# roundboard_-_MDBT42Q_ICM20848_new.net
KiCad netlist of a schematic drawn in EAGLE
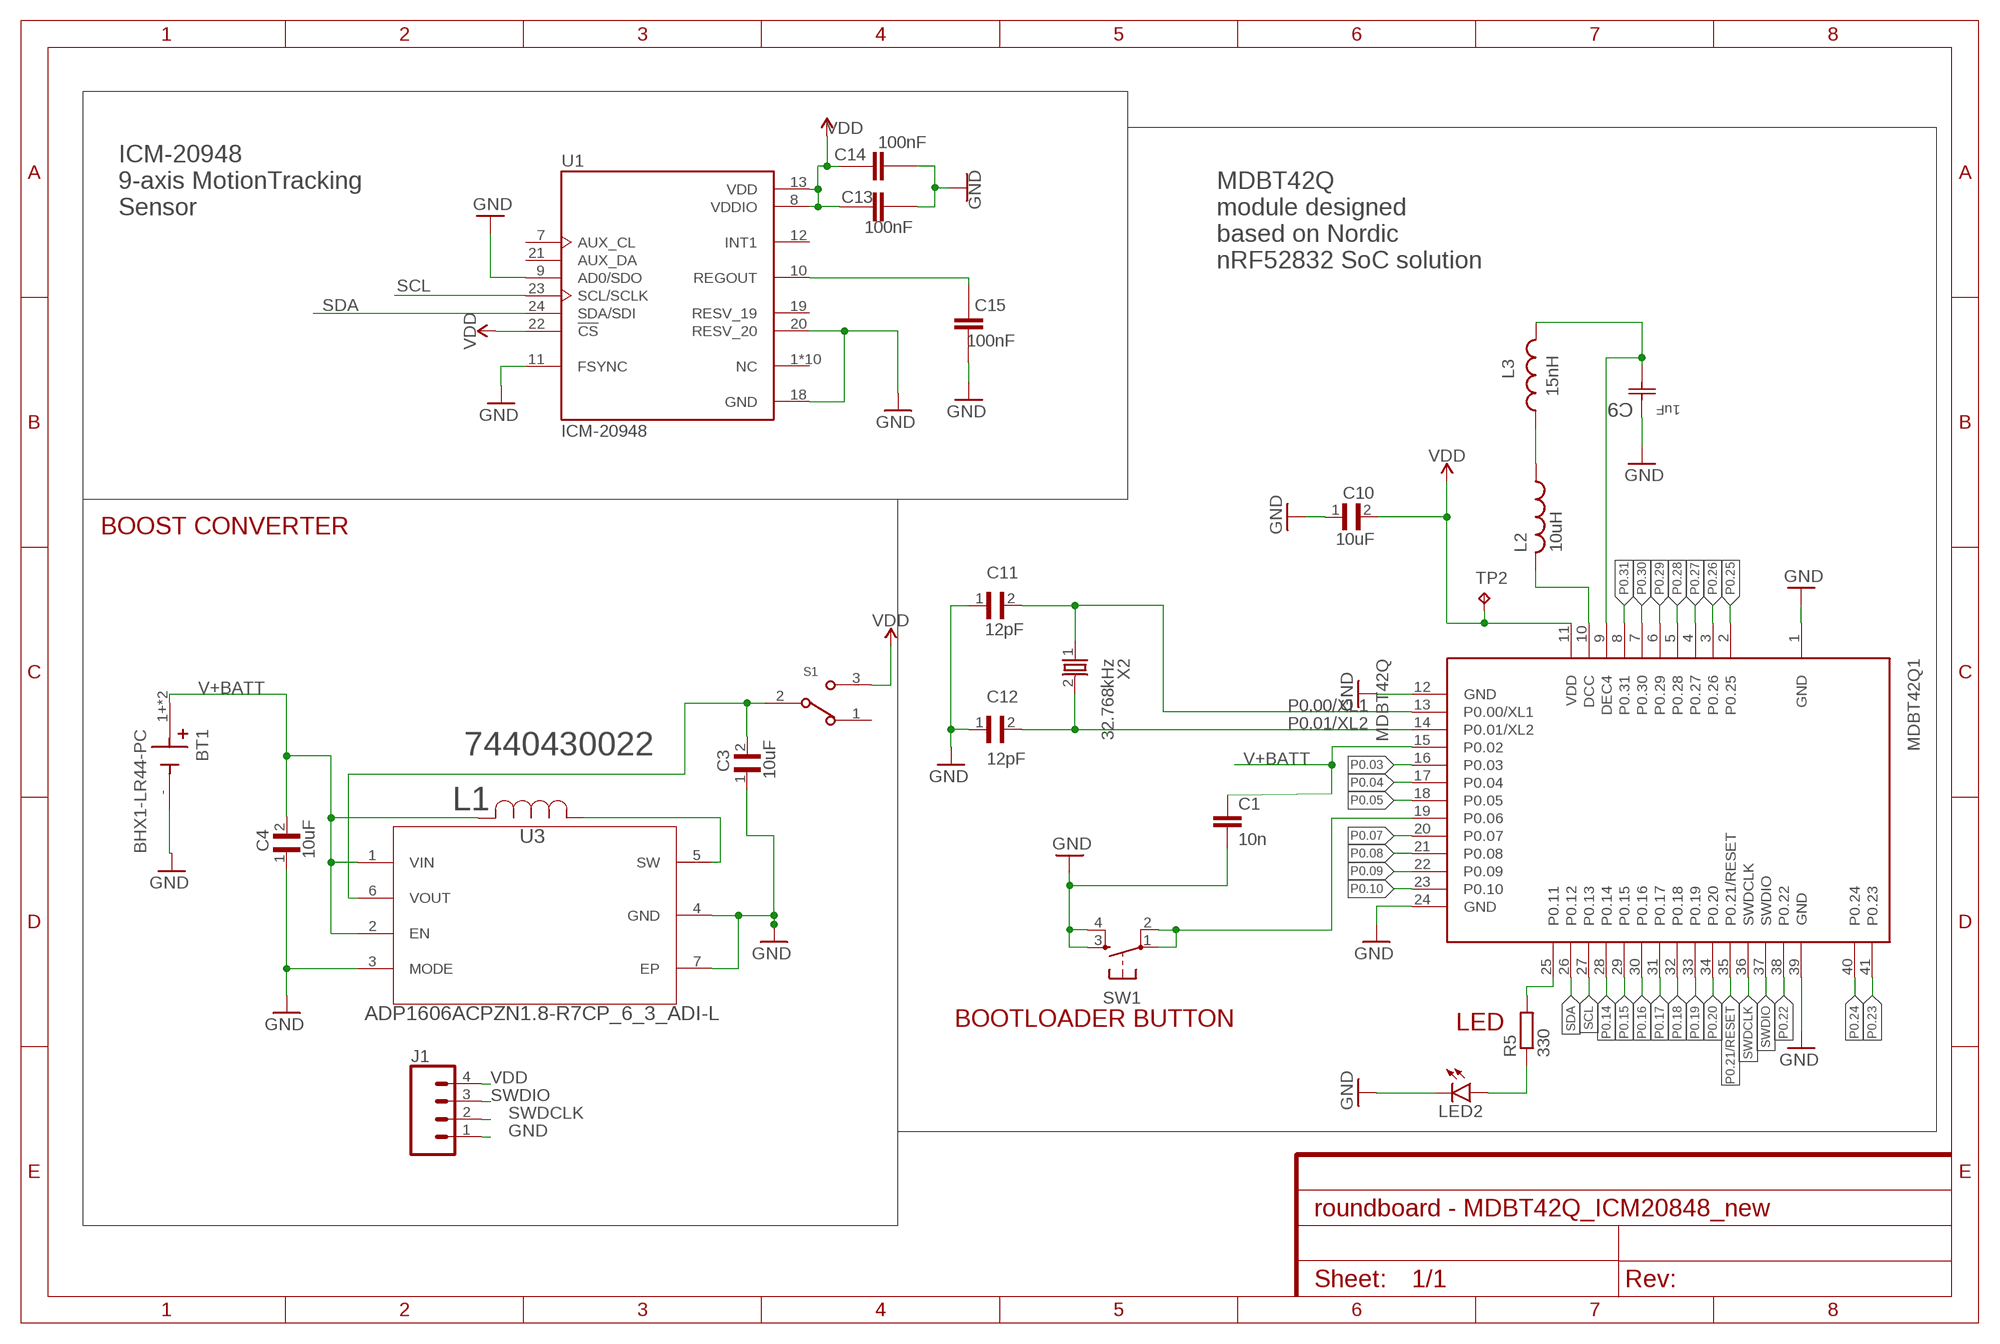
[diagram p0: schematic, sheet 1]

(export (version "E")
  (design (tool "Eeschema 10.0.6"))
  (components
    (comp (ref "BT1")
      (value "BHX1-LR44-PC")
      (footprint "eagle-import:BAT_BHX1-LR44-PC")
      (fields (field (name "DIGI-KEY_PART_NUMBER") "BHX1-LR44-PC-G-ND") (field (name "MF") "MPD"))
      (libsource (lib "eagle-import") (part "BHX1-LR44-PC"))
    )
    (comp (ref "C1")
      (value "10n")
      (footprint "eagle-import:C0603")
      (libsource (lib "eagle-import") (part "C-EUC0603"))
    )
    (comp (ref "C3")
      (value "10uF")
      (footprint "eagle-import:CAPC1608X95N")
      (fields
        (field (name "DIGI-KEY_PART_NUMBER") "490-14372-1-ND")
        (field (name "MF") "Murata")
        (field (name "MP") "GRM188R61A106KE69J")
      )
      (libsource (lib "eagle-import") (part "GRM188R61A106KE69J"))
    )
    (comp (ref "C4")
      (value "10uF")
      (footprint "eagle-import:CAPC1608X95N")
      (fields
        (field (name "DIGI-KEY_PART_NUMBER") "490-14372-1-ND")
        (field (name "MF") "Murata")
        (field (name "MP") "GRM188R61A106KE69J")
      )
      (libsource (lib "eagle-import") (part "GRM188R61A106KE69J"))
    )
    (comp (ref "C9")
      (value "1uF")
      (footprint "eagle-import:CAPC1608X90N")
      (fields
        (field (name "DIGI-KEY_PART_NUMBER") "311-1446-1-ND")
        (field (name "MF") "Yageo")
        (field (name "MP") "CC0603KRX7R7BB105")
      )
      (libsource (lib "eagle-import") (part "CC0603KRX7R7BB105"))
    )
    (comp (ref "C10")
      (value "10uF")
      (footprint "eagle-import:CAPC1608X95N")
      (fields
        (field (name "DIGI-KEY_PART_NUMBER") "490-14372-1-ND")
        (field (name "MF") "Murata")
        (field (name "MP") "GRM188R61A106KE69J")
      )
      (libsource (lib "eagle-import") (part "GRM188R61A106KE69J"))
    )
    (comp (ref "C11")
      (value "12pF")
      (footprint "eagle-import:CAPC1005X56N")
      (fields
        (field (name "DIGI-KEY_PART_NUMBER") "478-7871-1-ND")
        (field (name "MF") "AVX")
        (field (name "MP") "04025A120GAT2A")
      )
      (libsource (lib "eagle-import") (part "04025A120GAT2A"))
    )
    (comp (ref "C12")
      (value "12pF")
      (footprint "eagle-import:CAPC1005X56N")
      (fields
        (field (name "DIGI-KEY_PART_NUMBER") "478-7871-1-ND")
        (field (name "MF") "AVX")
        (field (name "MP") "04025A120GAT2A")
      )
      (libsource (lib "eagle-import") (part "04025A120GAT2A"))
    )
    (comp (ref "C13")
      (value "100nF")
      (footprint "eagle-import:CAPC1005X60")
      (fields
        (field (name "DIGI-KEY_PART_NUMBER") "311-1345-1-ND")
        (field (name "MF") "Yageo")
        (field (name "MP") "CC0402KRX7R6BB104")
      )
      (libsource (lib "eagle-import") (part "CC0402KRX7R6BB104"))
    )
    (comp (ref "C14")
      (value "100nF")
      (footprint "eagle-import:CAPC1005X60")
      (fields
        (field (name "DIGI-KEY_PART_NUMBER") "311-1345-1-ND")
        (field (name "MF") "Yageo")
        (field (name "MP") "CC0402KRX7R6BB104")
      )
      (libsource (lib "eagle-import") (part "CC0402KRX7R6BB104"))
    )
    (comp (ref "C15")
      (value "100nF")
      (footprint "eagle-import:CAPC1005X60")
      (fields
        (field (name "DIGI-KEY_PART_NUMBER") "311-1345-1-ND")
        (field (name "MF") "Yageo")
        (field (name "MP") "CC0402KRX7R6BB104")
      )
      (libsource (lib "eagle-import") (part "CC0402KRX7R6BB104"))
    )
    (comp (ref "J1")
      (value "CONN_04PTH")
      (footprint "eagle-import:1X04")
      (libsource (lib "eagle-import") (part "CONN_04PTH"))
    )
    (comp (ref "L1")
      (value "7440430022")
      (footprint "eagle-import:IND_7440430022_WRE")
      (fields (field (name "COPYRIGHT") "Copyright (C) 2018 Accelerated Designs. All rights reserved"))
      (libsource (lib "eagle-import") (part "7440430022"))
    )
    (comp (ref "L2")
      (value "10uH")
      (footprint "eagle-import:RESC0603_L")
      (libsource (lib "eagle-import") (part "INDUCTOR_0603_L"))
    )
    (comp (ref "L3")
      (value "15nH")
      (footprint "eagle-import:INDC1005X55N")
      (fields
        (field (name "DIGI-KEY_PART_NUMBER") "490-2625-1-ND")
        (field (name "MF") "Murata Electronics")
        (field (name "MP") "LQG15HS15NJ02D")
      )
      (libsource (lib "eagle-import") (part "LQG15HS15NJ02D"))
    )
    (comp (ref "LED2")
      (value "LEDCHIPLED_0603")
      (footprint "eagle-import:CHIPLED_0603")
      (libsource (lib "eagle-import") (part "LEDCHIPLED_0603"))
    )
    (comp (ref "MDBT42Q1")
      (value "MDBT42Q")
      (footprint "eagle-import:MDBT42Q")
      (libsource (lib "eagle-import") (part "MDBT42Q"))
    )
    (comp (ref "R5")
      (value "330")
      (footprint "eagle-import:R0603")
      (libsource (lib "eagle-import") (part "R-EU_R0603"))
    )
    (comp (ref "S1")
      (value "JS102011SAQN")
      (footprint "eagle-import:SW_JS102011SAQN")
      (fields (field (name "DIGI-KEY_PART_NUMBER") "401-1999-1-ND") (field (name "MF") "C&K"))
      (libsource (lib "eagle-import") (part "JS102011SAQN"))
    )
    (comp (ref "SW1")
      (value "SWITCH_SPST_4_PINRECT")
      (footprint "eagle-import:TACTILE_SWITCH_SMD_4.6X2.8MM")
      (libsource (lib "eagle-import") (part "SWITCH_SPST_4_PINRECT"))
    )
    (comp (ref "TP2")
      (value "TPB1,27")
      (footprint "eagle-import:B1,27")
      (libsource (lib "eagle-import") (part "TPB1,27"))
    )
    (comp (ref "U1")
      (value "ICM-20948")
      (footprint "eagle-import:QFN40P300X300X105-24N")
      (fields (field (name "MF") "TDK InvenSense"))
      (libsource (lib "eagle-import") (part "ICM-20948"))
    )
    (comp (ref "U3")
      (value "ADP1606ACPZN1.8-R7CP_6_3_ADI-L")
      (footprint "eagle-import:CP_6_3_ADI-L")
      (fields (field (name "MANUFACTURER_PART_NUMBER") "ADP1606ACPZN1.8-R7"))
      (libsource (lib "eagle-import") (part "ADP1606ACPZN1.8-R7CP_6_3_ADI-L"))
    )
    (comp (ref "X2")
      (value "32.768kHz")
      (footprint "eagle-import:XTAL_3215_N")
      (libsource (lib "eagle-import") (part "XTAL_32KHZ"))
    )
  )
  (nets
    (net (code "1") (name "/P0.00{slash}XL1") (class "Default")
      (node (ref "C11") (pin "2") (pinfunction "2_2") (pintype "passive"))
      (node (ref "MDBT42Q1") (pin "13") (pinfunction "P0.00/XL1_13") (pintype "bidirectional"))
      (node (ref "X2") (pin "1") (pinfunction "1_1") (pintype "passive"))
    )
    (net (code "2") (name "/P0.01{slash}XL2") (class "Default")
      (node (ref "C12") (pin "2") (pinfunction "2_2") (pintype "passive"))
      (node (ref "MDBT42Q1") (pin "14") (pinfunction "P0.01/XL2_14") (pintype "bidirectional"))
      (node (ref "X2") (pin "2") (pinfunction "2_2") (pintype "passive"))
    )
    (net (code "3") (name "/V+BATT") (class "Default")
      (node (ref "BT1") (pin "1+") (pinfunction "+_1+") (pintype "passive"))
      (node (ref "BT1") (pin "2+") (pinfunction "+_2+") (pintype "passive"))
      (node (ref "C1") (pin "1") (pinfunction "1_1") (pintype "passive"))
      (node (ref "C4") (pin "2") (pinfunction "2_2") (pintype "passive"))
      (node (ref "L1") (pin "2") (pinfunction "2_2") (pintype "passive"))
      (node (ref "MDBT42Q1") (pin "15") (pinfunction "P0.02_15") (pintype "bidirectional"))
      (node (ref "U3") (pin "1") (pinfunction "VIN_1") (pintype "passive"))
      (node (ref "U3") (pin "2") (pinfunction "EN_2") (pintype "passive"))
    )
    (net (code "4") (name "GND") (class "Default")
      (node (ref "BT1") (pin "-") (pinfunction "-_-") (pintype "passive"))
      (node (ref "C1") (pin "2") (pinfunction "2_2") (pintype "passive"))
      (node (ref "C10") (pin "1") (pinfunction "1_1") (pintype "passive"))
      (node (ref "C11") (pin "1") (pinfunction "1_1") (pintype "passive"))
      (node (ref "C12") (pin "1") (pinfunction "1_1") (pintype "passive"))
      (node (ref "C13") (pin "1") (pinfunction "1_1") (pintype "passive"))
      (node (ref "C14") (pin "1") (pinfunction "1_1") (pintype "passive"))
      (node (ref "C15") (pin "1") (pinfunction "1_1") (pintype "passive"))
      (node (ref "C3") (pin "1") (pinfunction "1_1") (pintype "passive"))
      (node (ref "C4") (pin "1") (pinfunction "1_1") (pintype "passive"))
      (node (ref "C9") (pin "1") (pinfunction "C1_1") (pintype "passive"))
      (node (ref "J1") (pin "1") (pinfunction "1_1") (pintype "passive"))
      (node (ref "LED2") (pin "C") (pinfunction "C_C") (pintype "passive"))
      (node (ref "MDBT42Q1") (pin "1") (pinfunction "GND_1") (pintype "bidirectional"))
      (node (ref "MDBT42Q1") (pin "12") (pinfunction "GND_12") (pintype "bidirectional"))
      (node (ref "MDBT42Q1") (pin "24") (pinfunction "GND_24") (pintype "bidirectional"))
      (node (ref "MDBT42Q1") (pin "39") (pinfunction "GND_39") (pintype "bidirectional"))
      (node (ref "SW1") (pin "3") (pinfunction "3_3") (pintype "passive"))
      (node (ref "SW1") (pin "4") (pinfunction "4_4") (pintype "passive"))
      (node (ref "U1") (pin "11") (pinfunction "FSYNC_11") (pintype "input"))
      (node (ref "U1") (pin "18") (pinfunction "GND_18") (pintype "power_in"))
      (node (ref "U1") (pin "20") (pinfunction "RESV_20_20") (pintype "passive"))
      (node (ref "U1") (pin "9") (pinfunction "AD0/SDO_9") (pintype "bidirectional"))
      (node (ref "U3") (pin "3") (pinfunction "MODE_3") (pintype "passive"))
      (node (ref "U3") (pin "4") (pinfunction "GND_4") (pintype "passive"))
      (node (ref "U3") (pin "7") (pinfunction "EP_7") (pintype "passive"))
    )
    (net (code "5") (name "Net-(C9-C2)") (class "Default")
      (node (ref "C9") (pin "2") (pinfunction "C2_2") (pintype "passive"))
      (node (ref "L3") (pin "2") (pinfunction "2_2") (pintype "passive"))
      (node (ref "MDBT42Q1") (pin "9") (pinfunction "DEC4_9") (pintype "bidirectional"))
    )
    (net (code "6") (name "Net-(L2-Pad1)") (class "Default")
      (node (ref "L2") (pin "1") (pinfunction "1_1") (pintype "passive"))
      (node (ref "L3") (pin "1") (pinfunction "1_1") (pintype "passive"))
    )
    (net (code "7") (name "Net-(LED2-PadA)") (class "Default")
      (node (ref "LED2") (pin "A") (pinfunction "A_A") (pintype "passive"))
      (node (ref "R5") (pin "1") (pinfunction "1_1") (pintype "passive"))
    )
    (net (code "8") (name "Net-(MDBT42Q1-DCC)") (class "Default")
      (node (ref "L2") (pin "2") (pinfunction "2_2") (pintype "passive"))
      (node (ref "MDBT42Q1") (pin "10") (pinfunction "DCC_10") (pintype "bidirectional"))
    )
    (net (code "9") (name "Net-(MDBT42Q1-P0.06)") (class "Default")
      (node (ref "MDBT42Q1") (pin "19") (pinfunction "P0.06_19") (pintype "bidirectional"))
      (node (ref "SW1") (pin "1") (pinfunction "1_1") (pintype "passive"))
      (node (ref "SW1") (pin "2") (pinfunction "2_2") (pintype "passive"))
    )
    (net (code "10") (name "Net-(MDBT42Q1-P0.11)") (class "Default")
      (node (ref "MDBT42Q1") (pin "25") (pinfunction "P0.11_25") (pintype "bidirectional"))
      (node (ref "R5") (pin "2") (pinfunction "2_2") (pintype "passive"))
    )
    (net (code "11") (name "Net-(U1-REGOUT)") (class "Default")
      (node (ref "C15") (pin "2") (pinfunction "2_2") (pintype "passive"))
      (node (ref "U1") (pin "10") (pinfunction "REGOUT_10") (pintype "output"))
    )
    (net (code "12") (name "Net-(U3-SW)") (class "Default")
      (node (ref "L1") (pin "1") (pinfunction "1_1") (pintype "passive"))
      (node (ref "U3") (pin "5") (pinfunction "SW_5") (pintype "passive"))
    )
    (net (code "13") (name "Net-(U3-VOUT)") (class "Default")
      (node (ref "C3") (pin "2") (pinfunction "2_2") (pintype "passive"))
      (node (ref "S1") (pin "2") (pinfunction "2_2") (pintype "passive"))
      (node (ref "U3") (pin "6") (pinfunction "VOUT_6") (pintype "passive"))
    )
    (net (code "14") (name "P0.03") (class "Default")
      (node (ref "MDBT42Q1") (pin "16") (pinfunction "P0.03_16") (pintype "bidirectional"))
    )
    (net (code "15") (name "P0.04") (class "Default")
      (node (ref "MDBT42Q1") (pin "17") (pinfunction "P0.04_17") (pintype "bidirectional"))
    )
    (net (code "16") (name "P0.05") (class "Default")
      (node (ref "MDBT42Q1") (pin "18") (pinfunction "P0.05_18") (pintype "bidirectional"))
    )
    (net (code "17") (name "P0.07") (class "Default")
      (node (ref "MDBT42Q1") (pin "20") (pinfunction "P0.07_20") (pintype "bidirectional"))
    )
    (net (code "18") (name "P0.08") (class "Default")
      (node (ref "MDBT42Q1") (pin "21") (pinfunction "P0.08_21") (pintype "bidirectional"))
    )
    (net (code "19") (name "P0.09") (class "Default")
      (node (ref "MDBT42Q1") (pin "22") (pinfunction "P0.09_22") (pintype "bidirectional"))
    )
    (net (code "20") (name "P0.10") (class "Default")
      (node (ref "MDBT42Q1") (pin "23") (pinfunction "P0.10_23") (pintype "bidirectional"))
    )
    (net (code "21") (name "P0.14") (class "Default")
      (node (ref "MDBT42Q1") (pin "28") (pinfunction "P0.14_28") (pintype "bidirectional"))
    )
    (net (code "22") (name "P0.15") (class "Default")
      (node (ref "MDBT42Q1") (pin "29") (pinfunction "P0.15_29") (pintype "bidirectional"))
    )
    (net (code "23") (name "P0.16") (class "Default")
      (node (ref "MDBT42Q1") (pin "30") (pinfunction "P0.16_30") (pintype "bidirectional"))
    )
    (net (code "24") (name "P0.17") (class "Default")
      (node (ref "MDBT42Q1") (pin "31") (pinfunction "P0.17_31") (pintype "bidirectional"))
    )
    (net (code "25") (name "P0.18") (class "Default")
      (node (ref "MDBT42Q1") (pin "32") (pinfunction "P0.18_32") (pintype "bidirectional"))
    )
    (net (code "26") (name "P0.19") (class "Default")
      (node (ref "MDBT42Q1") (pin "33") (pinfunction "P0.19_33") (pintype "bidirectional"))
    )
    (net (code "27") (name "P0.20") (class "Default")
      (node (ref "MDBT42Q1") (pin "34") (pinfunction "P0.20_34") (pintype "bidirectional"))
    )
    (net (code "28") (name "P0.21{slash}RESET") (class "Default")
      (node (ref "MDBT42Q1") (pin "35") (pinfunction "P0.21/RESET_35") (pintype "bidirectional"))
    )
    (net (code "29") (name "P0.22") (class "Default")
      (node (ref "MDBT42Q1") (pin "38") (pinfunction "P0.22_38") (pintype "bidirectional"))
    )
    (net (code "30") (name "P0.23") (class "Default")
      (node (ref "MDBT42Q1") (pin "41") (pinfunction "P0.23_41") (pintype "bidirectional"))
    )
    (net (code "31") (name "P0.24") (class "Default")
      (node (ref "MDBT42Q1") (pin "40") (pinfunction "P0.24_40") (pintype "bidirectional"))
    )
    (net (code "32") (name "P0.25") (class "Default")
      (node (ref "MDBT42Q1") (pin "2") (pinfunction "P0.25_2") (pintype "bidirectional"))
    )
    (net (code "33") (name "P0.26") (class "Default")
      (node (ref "MDBT42Q1") (pin "3") (pinfunction "P0.26_3") (pintype "bidirectional"))
    )
    (net (code "34") (name "P0.27") (class "Default")
      (node (ref "MDBT42Q1") (pin "4") (pinfunction "P0.27_4") (pintype "bidirectional"))
    )
    (net (code "35") (name "P0.28") (class "Default")
      (node (ref "MDBT42Q1") (pin "5") (pinfunction "P0.28_5") (pintype "bidirectional"))
    )
    (net (code "36") (name "P0.29") (class "Default")
      (node (ref "MDBT42Q1") (pin "6") (pinfunction "P0.29_6") (pintype "bidirectional"))
    )
    (net (code "37") (name "P0.30") (class "Default")
      (node (ref "MDBT42Q1") (pin "7") (pinfunction "P0.30_7") (pintype "bidirectional"))
    )
    (net (code "38") (name "P0.31") (class "Default")
      (node (ref "MDBT42Q1") (pin "8") (pinfunction "P0.31_8") (pintype "bidirectional"))
    )
    (net (code "39") (name "SCL") (class "Default")
      (node (ref "MDBT42Q1") (pin "27") (pinfunction "P0.13_27") (pintype "bidirectional"))
      (node (ref "U1") (pin "23") (pinfunction "SCL/SCLK_23") (pintype "input"))
    )
    (net (code "40") (name "SDA") (class "Default")
      (node (ref "MDBT42Q1") (pin "26") (pinfunction "P0.12_26") (pintype "bidirectional"))
      (node (ref "U1") (pin "24") (pinfunction "SDA/SDI_24") (pintype "bidirectional"))
    )
    (net (code "41") (name "SWDCLK") (class "Default")
      (node (ref "J1") (pin "2") (pinfunction "2_2") (pintype "passive"))
      (node (ref "MDBT42Q1") (pin "36") (pinfunction "SWDCLK_36") (pintype "bidirectional"))
    )
    (net (code "42") (name "SWDIO") (class "Default")
      (node (ref "J1") (pin "3") (pinfunction "3_3") (pintype "passive"))
      (node (ref "MDBT42Q1") (pin "37") (pinfunction "SWDIO_37") (pintype "bidirectional"))
    )
    (net (code "43") (name "VDD") (class "Default")
      (node (ref "C10") (pin "2") (pinfunction "2_2") (pintype "passive"))
      (node (ref "C13") (pin "2") (pinfunction "2_2") (pintype "passive"))
      (node (ref "C14") (pin "2") (pinfunction "2_2") (pintype "passive"))
      (node (ref "J1") (pin "4") (pinfunction "4_4") (pintype "passive"))
      (node (ref "MDBT42Q1") (pin "11") (pinfunction "VDD_11") (pintype "bidirectional"))
      (node (ref "S1") (pin "3") (pinfunction "3_3") (pintype "passive"))
      (node (ref "TP2") (pin "TP") (pinfunction "TP_TP") (pintype "input"))
      (node (ref "U1") (pin "13") (pinfunction "VDD_13") (pintype "power_in"))
      (node (ref "U1") (pin "22") (pinfunction "~{CS}_22") (pintype "input"))
      (node (ref "U1") (pin "8") (pinfunction "VDDIO_8") (pintype "power_in"))
    )
    (net (code "44") (name "unconnected-(S1-Pad1)") (class "Default")
      (node (ref "S1") (pin "1") (pinfunction "1_1") (pintype "passive"))
    )
    (net (code "45") (name "unconnected-(U1-AUX_CL-Pad7)") (class "Default")
      (node (ref "U1") (pin "7") (pinfunction "AUX_CL_7") (pintype "input"))
    )
    (net (code "46") (name "unconnected-(U1-AUX_DA-Pad21)") (class "Default")
      (node (ref "U1") (pin "21") (pinfunction "AUX_DA_21") (pintype "bidirectional"))
    )
    (net (code "47") (name "unconnected-(U1-INT1-Pad12)") (class "Default")
      (node (ref "U1") (pin "12") (pinfunction "INT1_12") (pintype "output"))
    )
    (net (code "48") (name "unconnected-(U1-NC-Pad1)") (class "Default")
      (node (ref "U1") (pin "1") (pinfunction "NC_1") (pintype "no_connect"))
    )
    (net (code "49") (name "unconnected-(U1-NC-Pad2)") (class "Default")
      (node (ref "U1") (pin "2") (pinfunction "NC_2") (pintype "no_connect"))
    )
    (net (code "50") (name "unconnected-(U1-NC-Pad3)") (class "Default")
      (node (ref "U1") (pin "3") (pinfunction "NC_3") (pintype "no_connect"))
    )
    (net (code "51") (name "unconnected-(U1-NC-Pad4)") (class "Default")
      (node (ref "U1") (pin "4") (pinfunction "NC_4") (pintype "no_connect"))
    )
    (net (code "52") (name "unconnected-(U1-NC-Pad5)") (class "Default")
      (node (ref "U1") (pin "5") (pinfunction "NC_5") (pintype "no_connect"))
    )
    (net (code "53") (name "unconnected-(U1-NC-Pad6)") (class "Default")
      (node (ref "U1") (pin "6") (pinfunction "NC_6") (pintype "no_connect"))
    )
    (net (code "54") (name "unconnected-(U1-NC-Pad14)") (class "Default")
      (node (ref "U1") (pin "14") (pinfunction "NC_14") (pintype "no_connect"))
    )
    (net (code "55") (name "unconnected-(U1-NC-Pad15)") (class "Default")
      (node (ref "U1") (pin "15") (pinfunction "NC_15") (pintype "no_connect"))
    )
    (net (code "56") (name "unconnected-(U1-NC-Pad16)") (class "Default")
      (node (ref "U1") (pin "16") (pinfunction "NC_16") (pintype "no_connect"))
    )
    (net (code "57") (name "unconnected-(U1-NC-Pad17)") (class "Default")
      (node (ref "U1") (pin "17") (pinfunction "NC_17") (pintype "no_connect"))
    )
    (net (code "58") (name "unconnected-(U1-RESV_19-Pad19)") (class "Default")
      (node (ref "U1") (pin "19") (pinfunction "RESV_19_19") (pintype "passive"))
    )
  )
)
